# 0_1.net
KiCad netlist of a schematic drawn in EAGLE
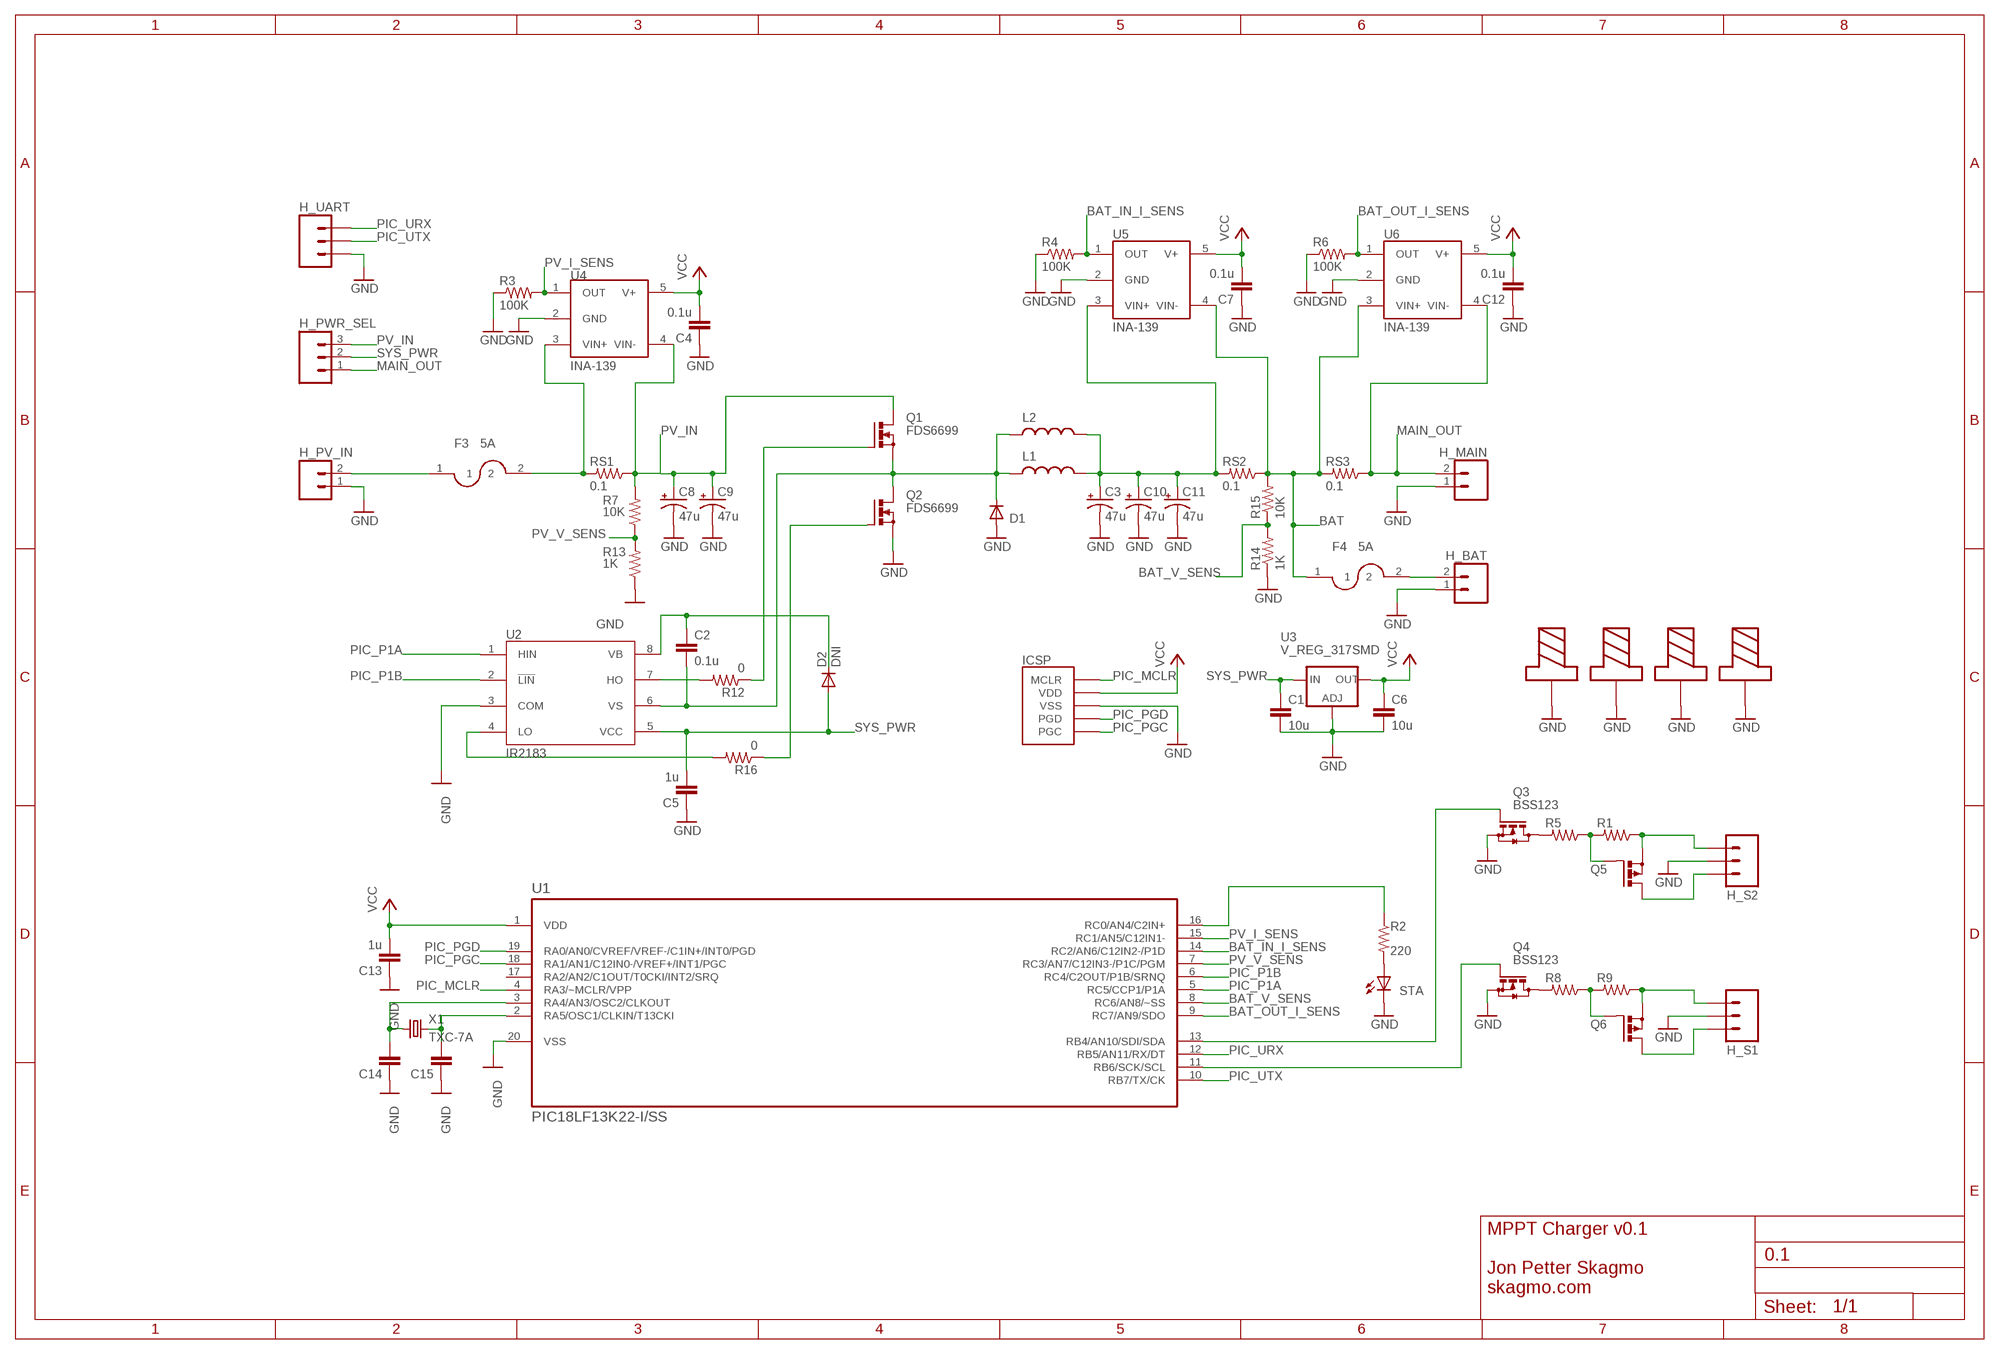
[diagram p0: schematic, sheet 1]

(export (version "E")
  (design (tool "Eeschema 10.0.6"))
  (components
    (comp (ref "C1")
      (value "10u")
      (footprint "eagle-import:C0805K")
      (libsource (lib "eagle-import") (part "C-EUC0805K"))
    )
    (comp (ref "C2")
      (value "0.1u")
      (footprint "eagle-import:0603")
      (libsource (lib "eagle-import") (part "CAP0603"))
    )
    (comp (ref "C3")
      (value "47u")
      (footprint "eagle-import:CT7343")
      (libsource (lib "eagle-import") (part "CAP_POLCT7343"))
    )
    (comp (ref "C4")
      (value "0.1u")
      (footprint "eagle-import:0603")
      (libsource (lib "eagle-import") (part "CAP0603"))
    )
    (comp (ref "C5")
      (value "1u")
      (footprint "eagle-import:0603")
      (libsource (lib "eagle-import") (part "CAP0603"))
    )
    (comp (ref "C6")
      (value "10u")
      (footprint "eagle-import:C0805K")
      (libsource (lib "eagle-import") (part "C-EUC0805K"))
    )
    (comp (ref "C7")
      (value "0.1u")
      (footprint "eagle-import:0603")
      (libsource (lib "eagle-import") (part "CAP0603"))
    )
    (comp (ref "C8")
      (value "47u")
      (footprint "eagle-import:CT7343")
      (libsource (lib "eagle-import") (part "CAP_POLCT7343"))
    )
    (comp (ref "C9")
      (value "47u")
      (footprint "eagle-import:CT7343")
      (libsource (lib "eagle-import") (part "CAP_POLCT7343"))
    )
    (comp (ref "C10")
      (value "47u")
      (footprint "eagle-import:CT7343")
      (libsource (lib "eagle-import") (part "CAP_POLCT7343"))
    )
    (comp (ref "C11")
      (value "47u")
      (footprint "eagle-import:CT7343")
      (libsource (lib "eagle-import") (part "CAP_POLCT7343"))
    )
    (comp (ref "C12")
      (value "0.1u")
      (footprint "eagle-import:0603")
      (libsource (lib "eagle-import") (part "CAP0603"))
    )
    (comp (ref "C13")
      (value "1u")
      (footprint "eagle-import:0603")
      (libsource (lib "eagle-import") (part "CAP0603"))
    )
    (comp (ref "C14")
      (value "CAP0603")
      (footprint "eagle-import:0603")
      (libsource (lib "eagle-import") (part "CAP0603"))
    )
    (comp (ref "C15")
      (value "CAP0603")
      (footprint "eagle-import:0603")
      (libsource (lib "eagle-import") (part "CAP0603"))
    )
    (comp (ref "D1")
      (value "DIODESMB")
      (footprint "eagle-import:SMB-DIODE")
      (libsource (lib "eagle-import") (part "SparkFun_DIODESMB"))
    )
    (comp (ref "D2")
      (value "DNI")
      (footprint "eagle-import:SOD-323")
      (libsource (lib "eagle-import") (part "DIODESOD"))
    )
    (comp (ref "F3")
      (value "5A")
      (footprint "eagle-import:1206")
      (libsource (lib "eagle-import") (part "FUSE1206"))
    )
    (comp (ref "F4")
      (value "5A")
      (footprint "eagle-import:1206")
      (libsource (lib "eagle-import") (part "FUSE1206"))
    )
    (comp (ref "H_BAT")
      (value "M023.5MM")
      (footprint "eagle-import:SCREWTERMINAL-3.5MM-2")
      (libsource (lib "eagle-import") (part "M023.5MM"))
    )
    (comp (ref "H_MAIN")
      (value "M023.5MM")
      (footprint "eagle-import:SCREWTERMINAL-3.5MM-2")
      (libsource (lib "eagle-import") (part "M023.5MM"))
    )
    (comp (ref "H_PV_IN")
      (value "M023.5MM")
      (footprint "eagle-import:SCREWTERMINAL-3.5MM-2")
      (libsource (lib "eagle-import") (part "M023.5MM"))
    )
    (comp (ref "H_PWR_SEL")
      (value "M03PTH")
      (footprint "eagle-import:1X03")
      (libsource (lib "eagle-import") (part "M03PTH"))
    )
    (comp (ref "H_S1")
      (value "1X3SCREW")
      (footprint "eagle-import:1X3_SCREW_0.1")
      (libsource (lib "eagle-import") (part "1X3SCREW"))
    )
    (comp (ref "H_S2")
      (value "1X3SCREW")
      (footprint "eagle-import:1X3_SCREW_0.1")
      (libsource (lib "eagle-import") (part "1X3SCREW"))
    )
    (comp (ref "H_UART")
      (value "1X3SCREW")
      (footprint "eagle-import:1X3_SCREW_0.1")
      (libsource (lib "eagle-import") (part "1X3SCREW"))
    )
    (comp (ref "ICSP")
      (value "1X5_ICSP")
      (footprint "eagle-import:1X5_2MM")
      (libsource (lib "eagle-import") (part "1X5_ICSP"))
    )
    (comp (ref "L1")
      (value "INDUCTORIHLP-6767")
      (footprint "eagle-import:IHLP-6767")
      (libsource (lib "eagle-import") (part "INDUCTORIHLP-6767"))
    )
    (comp (ref "L2")
      (value "INDUCTORIHLP-4040")
      (footprint "eagle-import:IHLP-4040")
      (libsource (lib "eagle-import") (part "INDUCTORIHLP-4040"))
    )
    (comp (ref "Q1")
      (value "FDS6699")
      (footprint "eagle-import:SO08")
      (libsource (lib "eagle-import") (part "PMOSFET_N"))
    )
    (comp (ref "Q2")
      (value "FDS6699")
      (footprint "eagle-import:SO08")
      (libsource (lib "eagle-import") (part "PMOSFET_N"))
    )
    (comp (ref "Q3")
      (value "BSS123")
      (footprint "eagle-import:SOT23")
      (libsource (lib "eagle-import") (part "BSS123"))
    )
    (comp (ref "Q4")
      (value "BSS123")
      (footprint "eagle-import:SOT23")
      (libsource (lib "eagle-import") (part "BSS123"))
    )
    (comp (ref "Q5")
      (value "PMOSFET_P")
      (footprint "eagle-import:SO08")
      (libsource (lib "eagle-import") (part "PMOSFET_P"))
    )
    (comp (ref "Q6")
      (value "PMOSFET_P")
      (footprint "eagle-import:SO08")
      (libsource (lib "eagle-import") (part "PMOSFET_P"))
    )
    (comp (ref "R1")
      (value "RESISTOR0603")
      (footprint "eagle-import:0603")
      (libsource (lib "eagle-import") (part "RESISTOR0603"))
    )
    (comp (ref "R2")
      (value "220")
      (footprint "eagle-import:0603")
      (libsource (lib "eagle-import") (part "RESISTOR0603"))
    )
    (comp (ref "R3")
      (value "100K")
      (footprint "eagle-import:0603")
      (libsource (lib "eagle-import") (part "RESISTOR0603"))
    )
    (comp (ref "R4")
      (value "100K")
      (footprint "eagle-import:0603")
      (libsource (lib "eagle-import") (part "RESISTOR0603"))
    )
    (comp (ref "R5")
      (value "RESISTOR0603")
      (footprint "eagle-import:0603")
      (libsource (lib "eagle-import") (part "RESISTOR0603"))
    )
    (comp (ref "R6")
      (value "100K")
      (footprint "eagle-import:0603")
      (libsource (lib "eagle-import") (part "RESISTOR0603"))
    )
    (comp (ref "R7")
      (value "10K")
      (footprint "eagle-import:0603")
      (libsource (lib "eagle-import") (part "RESISTOR0603"))
    )
    (comp (ref "R8")
      (value "RESISTOR0603")
      (footprint "eagle-import:0603")
      (libsource (lib "eagle-import") (part "RESISTOR0603"))
    )
    (comp (ref "R9")
      (value "RESISTOR0603")
      (footprint "eagle-import:0603")
      (libsource (lib "eagle-import") (part "RESISTOR0603"))
    )
    (comp (ref "R12")
      (value "0")
      (footprint "eagle-import:0603")
      (libsource (lib "eagle-import") (part "RESISTOR0603"))
    )
    (comp (ref "R13")
      (value "1K")
      (footprint "eagle-import:0603")
      (libsource (lib "eagle-import") (part "RESISTOR0603"))
    )
    (comp (ref "R14")
      (value "1K")
      (footprint "eagle-import:0603")
      (libsource (lib "eagle-import") (part "RESISTOR0603"))
    )
    (comp (ref "R15")
      (value "10K")
      (footprint "eagle-import:0603")
      (libsource (lib "eagle-import") (part "RESISTOR0603"))
    )
    (comp (ref "R16")
      (value "0")
      (footprint "eagle-import:0603")
      (libsource (lib "eagle-import") (part "RESISTOR0603"))
    )
    (comp (ref "RS1")
      (value "0.1")
      (footprint "eagle-import:1206")
      (libsource (lib "eagle-import") (part "RESISTOR1206"))
    )
    (comp (ref "RS2")
      (value "0.1")
      (footprint "eagle-import:1206")
      (libsource (lib "eagle-import") (part "RESISTOR1206"))
    )
    (comp (ref "RS3")
      (value "0.1")
      (footprint "eagle-import:1206")
      (libsource (lib "eagle-import") (part "RESISTOR1206"))
    )
    (comp (ref "STA")
      (value "LEDCHIPLED_0805")
      (footprint "eagle-import:CHIPLED_0805")
      (libsource (lib "eagle-import") (part "LEDCHIPLED_0805"))
    )
    (comp (ref "U$1")
      (value "CORNER_SCREW")
      (footprint "eagle-import:CORNER_SCREW")
      (libsource (lib "eagle-import") (part "CORNER_SCREW"))
    )
    (comp (ref "U$2")
      (value "CORNER_SCREW")
      (footprint "eagle-import:CORNER_SCREW")
      (libsource (lib "eagle-import") (part "CORNER_SCREW"))
    )
    (comp (ref "U$3")
      (value "CORNER_SCREW")
      (footprint "eagle-import:CORNER_SCREW")
      (libsource (lib "eagle-import") (part "CORNER_SCREW"))
    )
    (comp (ref "U$4")
      (value "CORNER_SCREW")
      (footprint "eagle-import:CORNER_SCREW")
      (libsource (lib "eagle-import") (part "CORNER_SCREW"))
    )
    (comp (ref "U1")
      (value "PIC18LF13K22-I/SS")
      (footprint "eagle-import:SOP65P780X200-20N")
      (libsource (lib "eagle-import") (part "PIC18LF13K22-I/SS"))
    )
    (comp (ref "U2")
      (value "IR2183")
      (footprint "eagle-import:SO08")
      (libsource (lib "eagle-import") (part "IR2183"))
    )
    (comp (ref "U3")
      (value "V_REG_317SMD")
      (footprint "eagle-import:SOT223")
      (libsource (lib "eagle-import") (part "V_REG_317SMD"))
    )
    (comp (ref "U4")
      (value "INA-139")
      (footprint "eagle-import:SOT23-5")
      (libsource (lib "eagle-import") (part "INA-169"))
    )
    (comp (ref "U5")
      (value "INA-139")
      (footprint "eagle-import:SOT23-5")
      (libsource (lib "eagle-import") (part "INA-169"))
    )
    (comp (ref "U6")
      (value "INA-139")
      (footprint "eagle-import:SOT23-5")
      (libsource (lib "eagle-import") (part "INA-169"))
    )
    (comp (ref "X1")
      (value "TXC-7A")
      (footprint "eagle-import:TXC-7A")
      (libsource (lib "eagle-import") (part "TXC-7A"))
    )
  )
  (nets
    (net (code "1") (name "/BAT") (class "Default")
      (node (ref "F4") (pin "1") (pinfunction "1_1") (pintype "bidirectional"))
      (node (ref "R15") (pin "2") (pinfunction "2_2") (pintype "passive"))
      (node (ref "RS2") (pin "1") (pinfunction "1_1") (pintype "passive"))
      (node (ref "RS3") (pin "2") (pinfunction "2_2") (pintype "passive"))
      (node (ref "U5") (pin "4") (pinfunction "VIN-_4") (pintype "bidirectional"))
      (node (ref "U6") (pin "3") (pinfunction "VIN+_3") (pintype "bidirectional"))
    )
    (net (code "2") (name "/BAT_IN_I_SENS") (class "Default")
      (node (ref "R4") (pin "2") (pinfunction "2_2") (pintype "passive"))
      (node (ref "U1") (pin "14") (pinfunction "RC2/AN6/C12IN2-/P1D_14") (pintype "bidirectional"))
      (node (ref "U5") (pin "1") (pinfunction "OUT_1") (pintype "bidirectional"))
    )
    (net (code "3") (name "/BAT_OUT_I_SENS") (class "Default")
      (node (ref "R6") (pin "2") (pinfunction "2_2") (pintype "passive"))
      (node (ref "U1") (pin "9") (pinfunction "RC7/AN9/SDO_9") (pintype "bidirectional"))
      (node (ref "U6") (pin "1") (pinfunction "OUT_1") (pintype "bidirectional"))
    )
    (net (code "4") (name "/BAT_V_SENS") (class "Default")
      (node (ref "R14") (pin "2") (pinfunction "2_2") (pintype "passive"))
      (node (ref "R15") (pin "1") (pinfunction "1_1") (pintype "passive"))
      (node (ref "U1") (pin "8") (pinfunction "RC6/AN8/~{SS}_8") (pintype "bidirectional"))
    )
    (net (code "5") (name "/MAIN_OUT") (class "Default")
      (node (ref "H_MAIN") (pin "2") (pinfunction "2_2") (pintype "passive"))
      (node (ref "H_PWR_SEL") (pin "1") (pinfunction "1_1") (pintype "passive"))
      (node (ref "RS3") (pin "1") (pinfunction "1_1") (pintype "passive"))
      (node (ref "U6") (pin "4") (pinfunction "VIN-_4") (pintype "bidirectional"))
    )
    (net (code "6") (name "/PIC_MCLR") (class "Default")
      (node (ref "ICSP") (pin "P$1") (pinfunction "MCLR_P$1") (pintype "bidirectional"))
      (node (ref "U1") (pin "4") (pinfunction "RA3/~{MCLR/VPP}_4") (pintype "input"))
    )
    (net (code "7") (name "/PIC_P1A") (class "Default")
      (node (ref "U1") (pin "5") (pinfunction "RC5/CCP1/P1A_5") (pintype "bidirectional"))
      (node (ref "U2") (pin "1") (pinfunction "HIN_1") (pintype "bidirectional"))
    )
    (net (code "8") (name "/PIC_P1B") (class "Default")
      (node (ref "U1") (pin "6") (pinfunction "RC4/C2OUT/P1B/SRNQ_6") (pintype "bidirectional"))
      (node (ref "U2") (pin "2") (pinfunction "~{LIN}_2") (pintype "bidirectional"))
    )
    (net (code "9") (name "/PIC_PGC") (class "Default")
      (node (ref "ICSP") (pin "P$5") (pinfunction "PGC_P$5") (pintype "bidirectional"))
      (node (ref "U1") (pin "18") (pinfunction "RA1/AN1/C12IN0-/VREF+/INT1/PGC_18") (pintype "bidirectional"))
    )
    (net (code "10") (name "/PIC_PGD") (class "Default")
      (node (ref "ICSP") (pin "P$4") (pinfunction "PGD_P$4") (pintype "bidirectional"))
      (node (ref "U1") (pin "19") (pinfunction "RA0/AN0/CVREF/VREF-/C1IN+/INT0/PGD_19") (pintype "bidirectional"))
    )
    (net (code "11") (name "/PIC_URX") (class "Default")
      (node (ref "H_UART") (pin "P$3") (pinfunction "3_P$3") (pintype "passive"))
      (node (ref "U1") (pin "12") (pinfunction "RB5/AN11/RX/DT_12") (pintype "bidirectional"))
    )
    (net (code "12") (name "/PIC_UTX") (class "Default")
      (node (ref "H_UART") (pin "P$2") (pinfunction "2_P$2") (pintype "passive"))
      (node (ref "U1") (pin "10") (pinfunction "RB7/TX/CK_10") (pintype "bidirectional"))
    )
    (net (code "13") (name "/PV_IN") (class "Default")
      (node (ref "C8") (pin "+") (pinfunction "+_+") (pintype "passive"))
      (node (ref "C9") (pin "+") (pinfunction "+_+") (pintype "passive"))
      (node (ref "H_PWR_SEL") (pin "3") (pinfunction "3_3") (pintype "passive"))
      (node (ref "Q1") (pin "5") (pinfunction "D_5") (pintype "passive"))
      (node (ref "Q1") (pin "6") (pinfunction "D_6") (pintype "passive"))
      (node (ref "Q1") (pin "7") (pinfunction "D_7") (pintype "passive"))
      (node (ref "Q1") (pin "8") (pinfunction "D_8") (pintype "passive"))
      (node (ref "R7") (pin "2") (pinfunction "2_2") (pintype "passive"))
      (node (ref "RS1") (pin "1") (pinfunction "1_1") (pintype "passive"))
      (node (ref "U4") (pin "4") (pinfunction "VIN-_4") (pintype "bidirectional"))
    )
    (net (code "14") (name "/PV_I_SENS") (class "Default")
      (node (ref "R3") (pin "2") (pinfunction "2_2") (pintype "passive"))
      (node (ref "U1") (pin "15") (pinfunction "RC1/AN5/C12IN1-_15") (pintype "bidirectional"))
      (node (ref "U4") (pin "1") (pinfunction "OUT_1") (pintype "bidirectional"))
    )
    (net (code "15") (name "/PV_V_SENS") (class "Default")
      (node (ref "R13") (pin "2") (pinfunction "2_2") (pintype "passive"))
      (node (ref "R7") (pin "1") (pinfunction "1_1") (pintype "passive"))
      (node (ref "U1") (pin "7") (pinfunction "RC3/AN7/C12IN3-/P1C/PGM_7") (pintype "bidirectional"))
    )
    (net (code "16") (name "/SYS_PWR") (class "Default")
      (node (ref "C1") (pin "1") (pinfunction "1_1") (pintype "passive"))
      (node (ref "C5") (pin "2") (pinfunction "2_2") (pintype "passive"))
      (node (ref "D2") (pin "2") (pinfunction "A_2") (pintype "passive"))
      (node (ref "H_PWR_SEL") (pin "2") (pinfunction "2_2") (pintype "passive"))
      (node (ref "U2") (pin "5") (pinfunction "VCC_5") (pintype "bidirectional"))
      (node (ref "U3") (pin "3") (pinfunction "IN_3") (pintype "input"))
    )
    (net (code "17") (name "GND") (class "Default")
      (node (ref "C1") (pin "2") (pinfunction "2_2") (pintype "passive"))
      (node (ref "C10") (pin "-") (pinfunction "-_-") (pintype "passive"))
      (node (ref "C11") (pin "-") (pinfunction "-_-") (pintype "passive"))
      (node (ref "C12") (pin "1") (pinfunction "1_1") (pintype "passive"))
      (node (ref "C13") (pin "1") (pinfunction "1_1") (pintype "passive"))
      (node (ref "C14") (pin "1") (pinfunction "1_1") (pintype "passive"))
      (node (ref "C15") (pin "1") (pinfunction "1_1") (pintype "passive"))
      (node (ref "C3") (pin "-") (pinfunction "-_-") (pintype "passive"))
      (node (ref "C4") (pin "1") (pinfunction "1_1") (pintype "passive"))
      (node (ref "C5") (pin "1") (pinfunction "1_1") (pintype "passive"))
      (node (ref "C6") (pin "2") (pinfunction "2_2") (pintype "passive"))
      (node (ref "C7") (pin "1") (pinfunction "1_1") (pintype "passive"))
      (node (ref "C8") (pin "-") (pinfunction "-_-") (pintype "passive"))
      (node (ref "C9") (pin "-") (pinfunction "-_-") (pintype "passive"))
      (node (ref "D1") (pin "A") (pinfunction "A_A") (pintype "passive"))
      (node (ref "H_BAT") (pin "1") (pinfunction "1_1") (pintype "passive"))
      (node (ref "H_MAIN") (pin "1") (pinfunction "1_1") (pintype "passive"))
      (node (ref "H_PV_IN") (pin "1") (pinfunction "1_1") (pintype "passive"))
      (node (ref "H_S1") (pin "P$2") (pinfunction "2_P$2") (pintype "passive"))
      (node (ref "H_S2") (pin "P$2") (pinfunction "2_P$2") (pintype "passive"))
      (node (ref "H_UART") (pin "P$1") (pinfunction "1_P$1") (pintype "passive"))
      (node (ref "ICSP") (pin "P$3") (pinfunction "VSS_P$3") (pintype "power_in"))
      (node (ref "Q2") (pin "1") (pinfunction "S_1") (pintype "passive"))
      (node (ref "Q2") (pin "2") (pinfunction "S_2") (pintype "passive"))
      (node (ref "Q2") (pin "3") (pinfunction "S_3") (pintype "passive"))
      (node (ref "Q3") (pin "2") (pinfunction "S_2") (pintype "passive"))
      (node (ref "Q4") (pin "2") (pinfunction "S_2") (pintype "passive"))
      (node (ref "R13") (pin "1") (pinfunction "1_1") (pintype "passive"))
      (node (ref "R14") (pin "1") (pinfunction "1_1") (pintype "passive"))
      (node (ref "R3") (pin "1") (pinfunction "1_1") (pintype "passive"))
      (node (ref "R4") (pin "1") (pinfunction "1_1") (pintype "passive"))
      (node (ref "R6") (pin "1") (pinfunction "1_1") (pintype "passive"))
      (node (ref "STA") (pin "C") (pinfunction "C_C") (pintype "passive"))
      (node (ref "U$1") (pin "P$1") (pinfunction "P$1_P$1") (pintype "bidirectional"))
      (node (ref "U$2") (pin "P$1") (pinfunction "P$1_P$1") (pintype "bidirectional"))
      (node (ref "U$3") (pin "P$1") (pinfunction "P$1_P$1") (pintype "bidirectional"))
      (node (ref "U$4") (pin "P$1") (pinfunction "P$1_P$1") (pintype "bidirectional"))
      (node (ref "U1") (pin "20") (pinfunction "VSS_20") (pintype "power_in"))
      (node (ref "U2") (pin "3") (pinfunction "COM_3") (pintype "bidirectional"))
      (node (ref "U3") (pin "1") (pinfunction "ADJ_1") (pintype "input"))
      (node (ref "U4") (pin "2") (pinfunction "GND_2") (pintype "bidirectional"))
      (node (ref "U5") (pin "2") (pinfunction "GND_2") (pintype "bidirectional"))
      (node (ref "U6") (pin "2") (pinfunction "GND_2") (pintype "bidirectional"))
    )
    (net (code "18") (name "Net-(D2-C)") (class "Default")
      (node (ref "C2") (pin "1") (pinfunction "1_1") (pintype "passive"))
      (node (ref "D2") (pin "1") (pinfunction "C_1") (pintype "passive"))
      (node (ref "U2") (pin "8") (pinfunction "VB_8") (pintype "bidirectional"))
    )
    (net (code "19") (name "Net-(F3-Pad1)") (class "Default")
      (node (ref "F3") (pin "1") (pinfunction "1_1") (pintype "bidirectional"))
      (node (ref "H_PV_IN") (pin "2") (pinfunction "2_2") (pintype "passive"))
    )
    (net (code "20") (name "Net-(F4-Pad2)") (class "Default")
      (node (ref "F4") (pin "2") (pinfunction "2_2") (pintype "bidirectional"))
      (node (ref "H_BAT") (pin "2") (pinfunction "2_2") (pintype "passive"))
    )
    (net (code "21") (name "Net-(H_S1-1)") (class "Default")
      (node (ref "H_S1") (pin "P$1") (pinfunction "1_P$1") (pintype "passive"))
      (node (ref "Q6") (pin "1") (pinfunction "S_1") (pintype "passive"))
      (node (ref "Q6") (pin "2") (pinfunction "S_2") (pintype "passive"))
      (node (ref "Q6") (pin "3") (pinfunction "S_3") (pintype "passive"))
      (node (ref "R9") (pin "1") (pinfunction "1_1") (pintype "passive"))
    )
    (net (code "22") (name "Net-(H_S1-3)") (class "Default")
      (node (ref "H_S1") (pin "P$3") (pinfunction "3_P$3") (pintype "passive"))
      (node (ref "Q6") (pin "5") (pinfunction "D_5") (pintype "passive"))
      (node (ref "Q6") (pin "6") (pinfunction "D_6") (pintype "passive"))
      (node (ref "Q6") (pin "7") (pinfunction "D_7") (pintype "passive"))
      (node (ref "Q6") (pin "8") (pinfunction "D_8") (pintype "passive"))
    )
    (net (code "23") (name "Net-(H_S2-1)") (class "Default")
      (node (ref "H_S2") (pin "P$1") (pinfunction "1_P$1") (pintype "passive"))
      (node (ref "Q5") (pin "1") (pinfunction "S_1") (pintype "passive"))
      (node (ref "Q5") (pin "2") (pinfunction "S_2") (pintype "passive"))
      (node (ref "Q5") (pin "3") (pinfunction "S_3") (pintype "passive"))
      (node (ref "R1") (pin "1") (pinfunction "1_1") (pintype "passive"))
    )
    (net (code "24") (name "Net-(H_S2-3)") (class "Default")
      (node (ref "H_S2") (pin "P$3") (pinfunction "3_P$3") (pintype "passive"))
      (node (ref "Q5") (pin "5") (pinfunction "D_5") (pintype "passive"))
      (node (ref "Q5") (pin "6") (pinfunction "D_6") (pintype "passive"))
      (node (ref "Q5") (pin "7") (pinfunction "D_7") (pintype "passive"))
      (node (ref "Q5") (pin "8") (pinfunction "D_8") (pintype "passive"))
    )
    (net (code "25") (name "Net-(L1-1)") (class "Default")
      (node (ref "C2") (pin "2") (pinfunction "2_2") (pintype "passive"))
      (node (ref "D1") (pin "C") (pinfunction "C_C") (pintype "passive"))
      (node (ref "L1") (pin "P$1") (pinfunction "1_P$1") (pintype "passive"))
      (node (ref "L2") (pin "1") (pinfunction "1_1") (pintype "passive"))
      (node (ref "Q1") (pin "1") (pinfunction "S_1") (pintype "passive"))
      (node (ref "Q1") (pin "2") (pinfunction "S_2") (pintype "passive"))
      (node (ref "Q1") (pin "3") (pinfunction "S_3") (pintype "passive"))
      (node (ref "Q2") (pin "5") (pinfunction "D_5") (pintype "passive"))
      (node (ref "Q2") (pin "6") (pinfunction "D_6") (pintype "passive"))
      (node (ref "Q2") (pin "7") (pinfunction "D_7") (pintype "passive"))
      (node (ref "Q2") (pin "8") (pinfunction "D_8") (pintype "passive"))
      (node (ref "U2") (pin "6") (pinfunction "VS_6") (pintype "bidirectional"))
    )
    (net (code "26") (name "Net-(L1-2)") (class "Default")
      (node (ref "C10") (pin "+") (pinfunction "+_+") (pintype "passive"))
      (node (ref "C11") (pin "+") (pinfunction "+_+") (pintype "passive"))
      (node (ref "C3") (pin "+") (pinfunction "+_+") (pintype "passive"))
      (node (ref "L1") (pin "P$2") (pinfunction "2_P$2") (pintype "passive"))
      (node (ref "L2") (pin "2") (pinfunction "2_2") (pintype "passive"))
      (node (ref "RS2") (pin "2") (pinfunction "2_2") (pintype "passive"))
      (node (ref "U5") (pin "3") (pinfunction "VIN+_3") (pintype "bidirectional"))
    )
    (net (code "27") (name "Net-(Q1-G)") (class "Default")
      (node (ref "Q1") (pin "4") (pinfunction "G_4") (pintype "passive"))
      (node (ref "R12") (pin "1") (pinfunction "1_1") (pintype "passive"))
    )
    (net (code "28") (name "Net-(Q2-G)") (class "Default")
      (node (ref "Q2") (pin "4") (pinfunction "G_4") (pintype "passive"))
      (node (ref "R16") (pin "1") (pinfunction "1_1") (pintype "passive"))
    )
    (net (code "29") (name "Net-(Q3-D)") (class "Default")
      (node (ref "Q3") (pin "3") (pinfunction "D_3") (pintype "passive"))
      (node (ref "R5") (pin "2") (pinfunction "2_2") (pintype "passive"))
    )
    (net (code "30") (name "Net-(Q3-G)") (class "Default")
      (node (ref "Q3") (pin "1") (pinfunction "G_1") (pintype "passive"))
      (node (ref "U1") (pin "13") (pinfunction "RB4/AN10/SDI/SDA_13") (pintype "bidirectional"))
    )
    (net (code "31") (name "Net-(Q4-D)") (class "Default")
      (node (ref "Q4") (pin "3") (pinfunction "D_3") (pintype "passive"))
      (node (ref "R8") (pin "2") (pinfunction "2_2") (pintype "passive"))
    )
    (net (code "32") (name "Net-(Q4-G)") (class "Default")
      (node (ref "Q4") (pin "1") (pinfunction "G_1") (pintype "passive"))
      (node (ref "U1") (pin "11") (pinfunction "RB6/SCK/SCL_11") (pintype "bidirectional"))
    )
    (net (code "33") (name "Net-(Q5-G)") (class "Default")
      (node (ref "Q5") (pin "4") (pinfunction "G_4") (pintype "passive"))
      (node (ref "R1") (pin "2") (pinfunction "2_2") (pintype "passive"))
      (node (ref "R5") (pin "1") (pinfunction "1_1") (pintype "passive"))
    )
    (net (code "34") (name "Net-(Q6-G)") (class "Default")
      (node (ref "Q6") (pin "4") (pinfunction "G_4") (pintype "passive"))
      (node (ref "R8") (pin "1") (pinfunction "1_1") (pintype "passive"))
      (node (ref "R9") (pin "2") (pinfunction "2_2") (pintype "passive"))
    )
    (net (code "35") (name "Net-(R2-Pad2)") (class "Default")
      (node (ref "R2") (pin "2") (pinfunction "2_2") (pintype "passive"))
      (node (ref "STA") (pin "A") (pinfunction "A_A") (pintype "passive"))
    )
    (net (code "36") (name "Net-(U1-RA4{slash}AN3{slash}OSC2{slash}CLKOUT)") (class "Default")
      (node (ref "C14") (pin "2") (pinfunction "2_2") (pintype "passive"))
      (node (ref "U1") (pin "3") (pinfunction "RA4/AN3/OSC2/CLKOUT_3") (pintype "bidirectional"))
      (node (ref "X1") (pin "1") (pinfunction "1_1") (pintype "passive"))
    )
    (net (code "37") (name "Net-(U1-RA5{slash}OSC1{slash}CLKIN{slash}T13CKI)") (class "Default")
      (node (ref "C15") (pin "2") (pinfunction "2_2") (pintype "passive"))
      (node (ref "U1") (pin "2") (pinfunction "RA5/OSC1/CLKIN/T13CKI_2") (pintype "bidirectional"))
      (node (ref "X1") (pin "2") (pinfunction "2_2") (pintype "passive"))
    )
    (net (code "38") (name "Net-(U1-RC0{slash}AN4{slash}C2IN+)") (class "Default")
      (node (ref "R2") (pin "1") (pinfunction "1_1") (pintype "passive"))
      (node (ref "U1") (pin "16") (pinfunction "RC0/AN4/C2IN+_16") (pintype "bidirectional"))
    )
    (net (code "39") (name "Net-(U2-HO)") (class "Default")
      (node (ref "R12") (pin "2") (pinfunction "2_2") (pintype "passive"))
      (node (ref "U2") (pin "7") (pinfunction "HO_7") (pintype "bidirectional"))
    )
    (net (code "40") (name "Net-(U2-LO)") (class "Default")
      (node (ref "R16") (pin "2") (pinfunction "2_2") (pintype "passive"))
      (node (ref "U2") (pin "4") (pinfunction "LO_4") (pintype "bidirectional"))
    )
    (net (code "41") (name "Net-(U4-VIN+)") (class "Default")
      (node (ref "F3") (pin "2") (pinfunction "2_2") (pintype "bidirectional"))
      (node (ref "RS1") (pin "2") (pinfunction "2_2") (pintype "passive"))
      (node (ref "U4") (pin "3") (pinfunction "VIN+_3") (pintype "bidirectional"))
    )
    (net (code "42") (name "VCC") (class "Default")
      (node (ref "C12") (pin "2") (pinfunction "2_2") (pintype "passive"))
      (node (ref "C13") (pin "2") (pinfunction "2_2") (pintype "passive"))
      (node (ref "C4") (pin "2") (pinfunction "2_2") (pintype "passive"))
      (node (ref "C6") (pin "1") (pinfunction "1_1") (pintype "passive"))
      (node (ref "C7") (pin "2") (pinfunction "2_2") (pintype "passive"))
      (node (ref "ICSP") (pin "P$2") (pinfunction "VDD_P$2") (pintype "power_in"))
      (node (ref "U1") (pin "1") (pinfunction "VDD_1") (pintype "power_in"))
      (node (ref "U3") (pin "2") (pinfunction "OUT_2") (pintype "output"))
      (node (ref "U4") (pin "5") (pinfunction "V+_5") (pintype "bidirectional"))
      (node (ref "U5") (pin "5") (pinfunction "V+_5") (pintype "bidirectional"))
      (node (ref "U6") (pin "5") (pinfunction "V+_5") (pintype "bidirectional"))
    )
    (net (code "43") (name "unconnected-(U1-RA2{slash}AN2{slash}C1OUT{slash}T0CKI{slash}INT2{slash}SRQ-Pad17)") (class "Default")
      (node (ref "U1") (pin "17") (pinfunction "RA2/AN2/C1OUT/T0CKI/INT2/SRQ_17") (pintype "input"))
    )
  )
)
